# POWER_CONTROL.net
KiCad netlist of a schematic drawn in Altium Designer
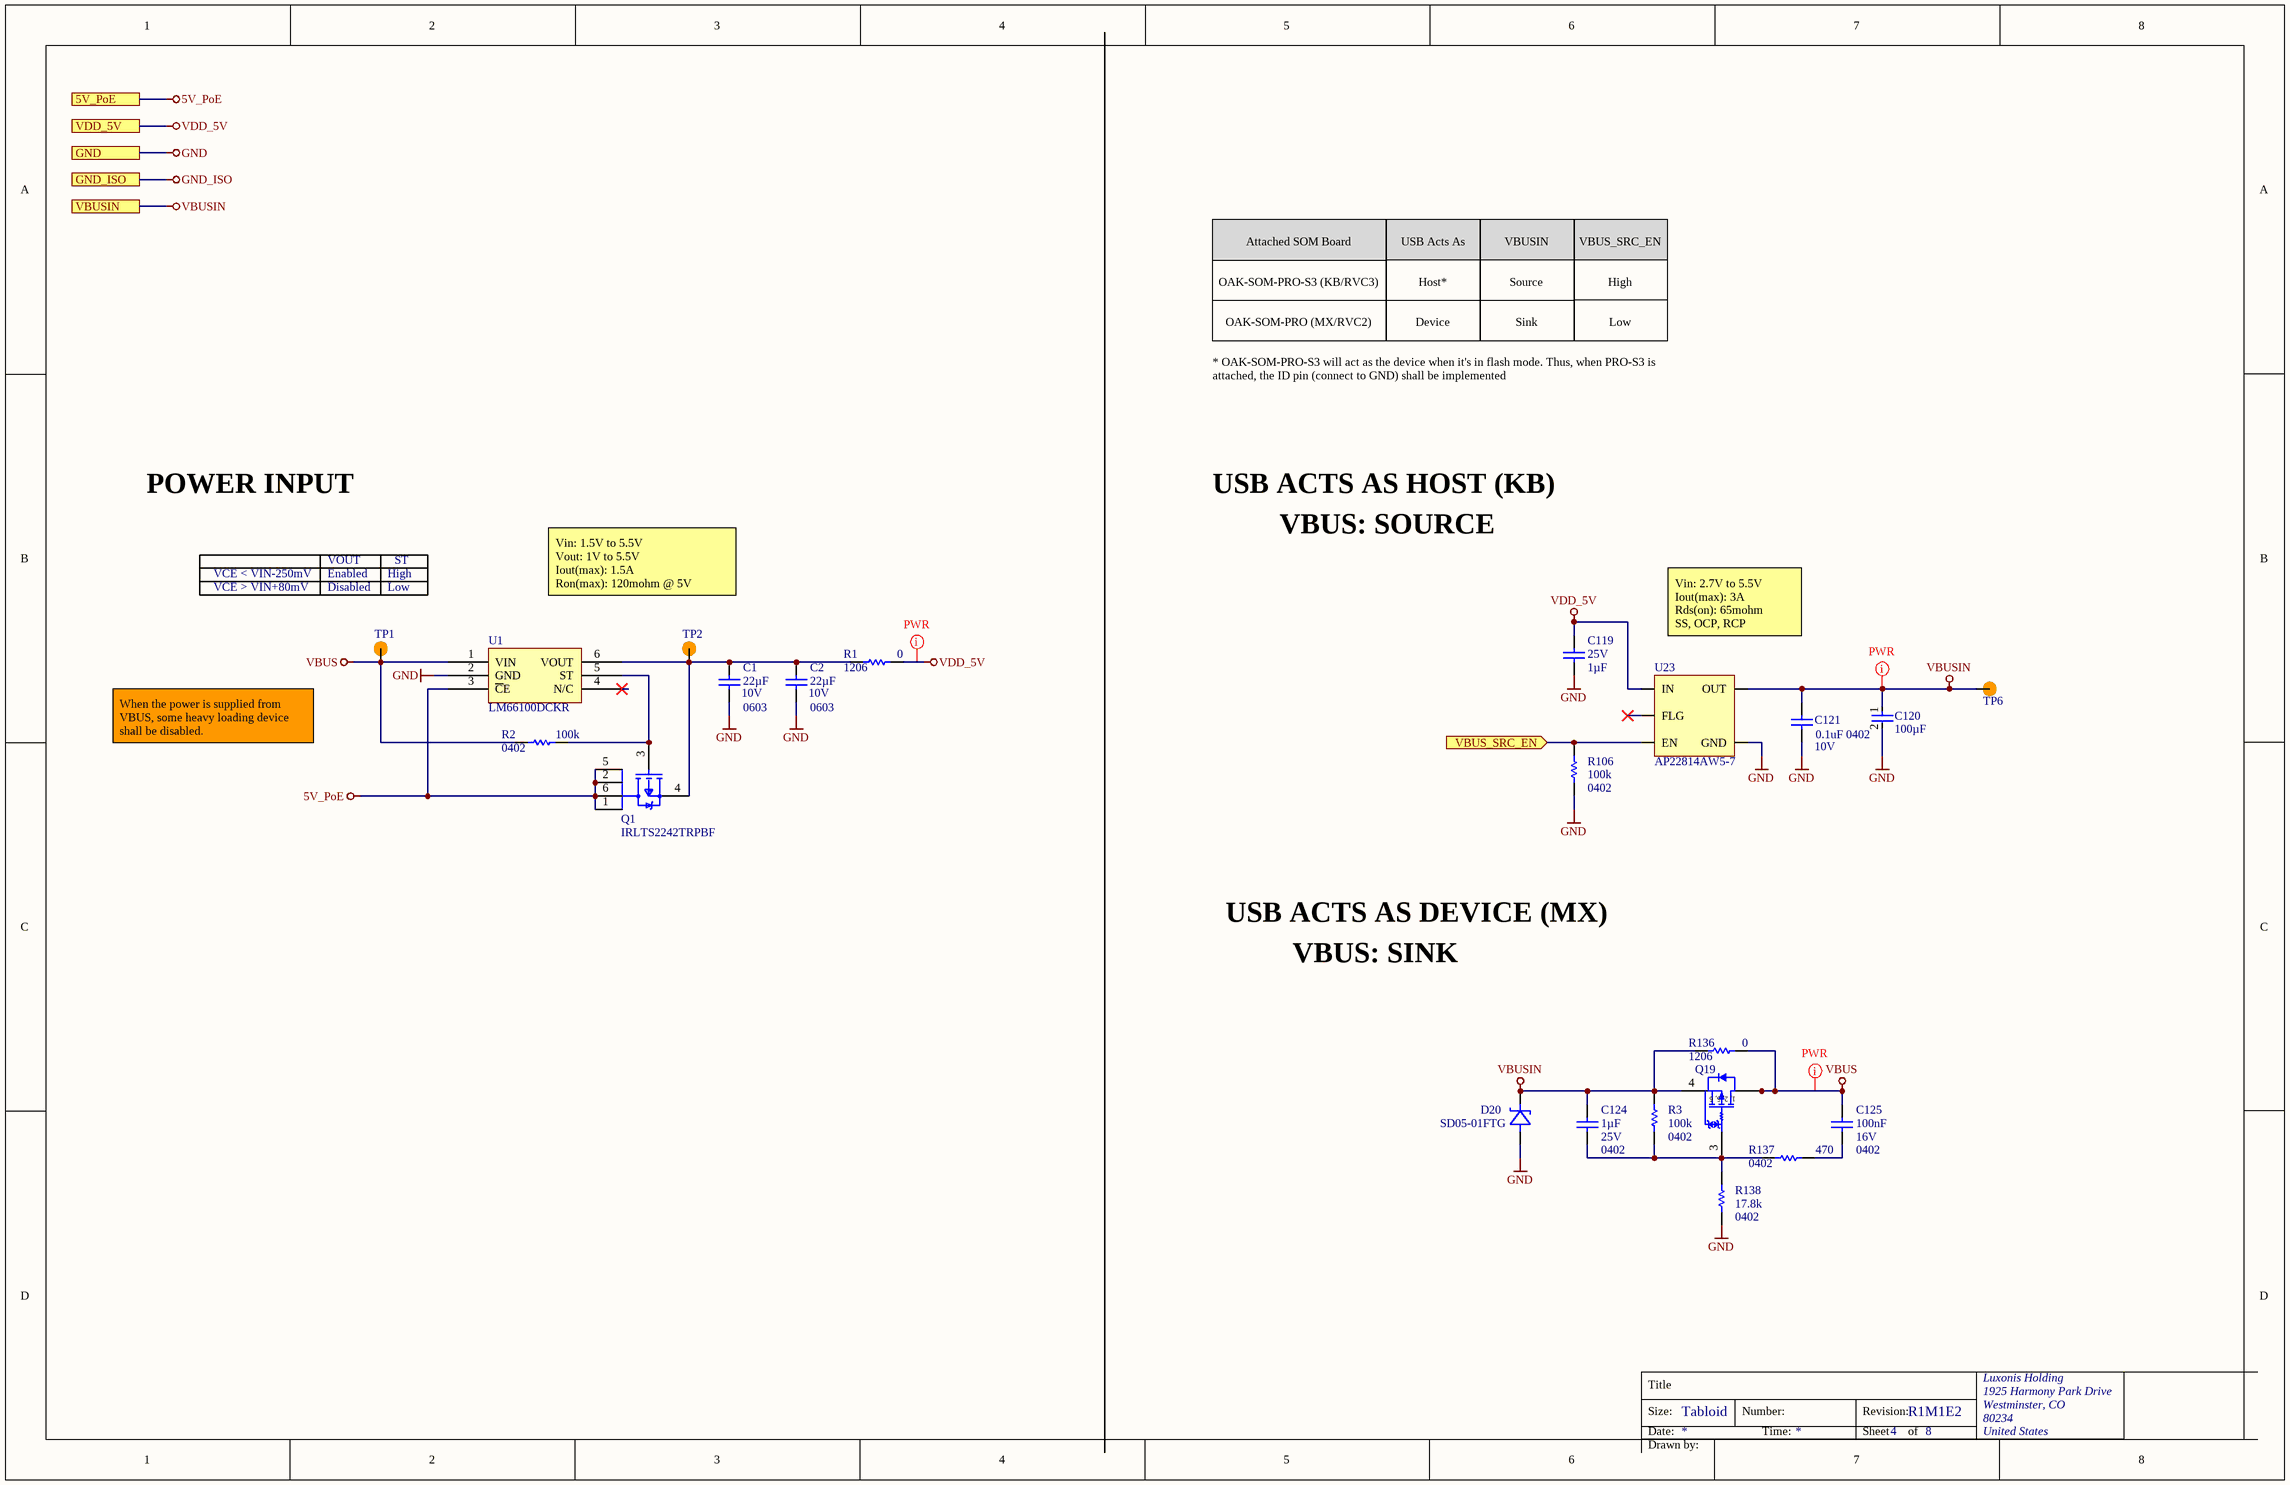
[diagram p0: POWER CONTROL.SchDoc]

(export (version "E")
  (design (tool "Eeschema 10.0.6"))
  (components
    (comp (ref "C1")
      (value "22µF")
      (footprint "CAPC0603(1608)100_N")
      (description "CAP CER 22UF 10V X5R 0603 20%")
      (fields
        (field (name "VOLTAGE RATING") "10V")
        (field (name "TOLERANCE") "20%")
        (field (name "CASE/PACKAGE") "0603")
        (field (name "Comment") "GRM188R61A226ME15D")
      )
      (libsource (lib "Luxonis LLC") (part "GRM188R61C475KAAJD"))
    )
    (comp (ref "C2")
      (value "22µF")
      (footprint "CAPC0603(1608)100_N")
      (description "CAP CER 22UF 10V X5R 0603 20%")
      (fields
        (field (name "VOLTAGE RATING") "10V")
        (field (name "TOLERANCE") "20%")
        (field (name "CASE/PACKAGE") "0603")
        (field (name "Comment") "GRM188R61A226ME15D")
      )
      (libsource (lib "Luxonis LLC") (part "GRM188R61C475KAAJD"))
    )
    (comp (ref "C119")
      (value "1µF")
      (footprint "CAPC0402(1005)70_N")
      (description "CAP CER 1UF 25V X5R 0402 10%")
      (fields
        (field (name "VOLTAGE RATING") "25V")
        (field (name "TOLERANCE") "10%")
        (field (name "Comment") "GRM155R61E105KA12D")
      )
      (libsource (lib "Luxonis LLC") (part "GRM188R61C475KAAJD"))
    )
    (comp (ref "C120")
      (value "100µF")
      (footprint "FP-C1210C107M8PACTU-MFG")
      (description "CAP CER 100UF 10V X5R 1210 20%")
      (fields (field (name "TOLERANCE") "20%") (field (name "Comment") "C1210C107M8PACTU"))
      (libsource (lib "Luxonis LLC") (part "b4654b650e69147ec39a6b967a45e02"))
    )
    (comp (ref "C121")
      (value "0.1uF 0402")
      (footprint "CAP_Altium_Vault_Generic:CAPC0402(1005)70_N")
      (description "CAP CER 0.1UF 10V X7R 0402 5%")
      (fields (field (name "TOLERANCE") "5%") (field (name "VOLTAGE RATING") "10V"))
      (libsource (lib "LuxonisMaster") (part "GRM155R71A104JA01D"))
    )
    (comp (ref "C124")
      (value "1µF")
      (footprint "CAPC0402(1005)70_N")
      (description "CAP CER 1UF 25V X5R 0402 10%")
      (fields
        (field (name "VOLTAGE RATING") "25V")
        (field (name "CASE/PACKAGE") "0402")
        (field (name "TOLERANCE") "10%")
        (field (name "Comment") "GRM155R61E105KA12D")
      )
      (libsource (lib "Luxonis LLC") (part "GRM188R61C475KAAJD"))
    )
    (comp (ref "C125")
      (value "100nF")
      (footprint "CAPC0402(1005)60_N")
      (description "CAP CER 0.1UF 16V X7R 0402 10%")
      (fields
        (field (name "VOLTAGE RATING") "16V")
        (field (name "CASE/PACKAGE") "0402")
        (field (name "TOLERANCE") "10%")
        (field (name "Comment") "CL05B104KO5NFNC")
      )
      (libsource (lib "Luxonis LLC") (part "GRM188R61C475KAAJD"))
    )
    (comp (ref "D20")
      (value "SD05-01FTG")
      (footprint "SD05-01FTG-Footprint-1")
      (description "Trans Voltage Suppressor Diode, 450W, 5V V(RWM), Unidirectional, 1 Element")
      (libsource (lib "Luxonis LLC") (part "SD05-01FTG"))
    )
    (comp (ref "Q1")
      (value "IRLTS2242TRPBF")
      (footprint "TSOP-6-MFG")
      (description "MOSFET P-CH 20V 6.9A 6TSOP")
      (libsource (lib "Luxonis LLC") (part "IRLTS2242TRPBF"))
    )
    (comp (ref "Q19")
      (value "NTJS4151PT1G")
      (footprint "ONSC-SC70-6-419B-02_W_V")
      (description "Trench Power MOSFET, -20 V, -4.2 A, Single P-Channel, 6-Pin SC70, Pb-Free, Tape and Reel")
      (libsource (lib "Luxonis LLC") (part "NTJS4151PT1G"))
    )
    (comp (ref "R1")
      (value "0")
      (footprint "RESC3116X70X50ML13T20")
      (description "RES SMD 0 OHM 5% 0.25W 1206")
      (fields
        (field (name "CASE/PACKAGE") "1206")
        (field (name "TOLERANCE") "5%")
        (field (name "Comment") "ERJ8GEY0R00V")
      )
      (libsource (lib "Luxonis LLC") (part "Default resistor symbol"))
    )
    (comp (ref "R2")
      (value "100k")
      (footprint "RESC0402(1005)_L")
      (description "RES SMD 100K OHM 1% 1/16W 0402")
      (fields
        (field (name "CASE/PACKAGE") "0402")
        (field (name "TOLERANCE") "1%")
        (field (name "Comment") "RC0402FR-07100KL")
      )
      (libsource (lib "Luxonis LLC") (part "Default resistor symbol"))
    )
    (comp (ref "R3")
      (value "100k")
      (footprint "RESC0402(1005)_L")
      (description "RES SMD 100K OHM 1% 1/16W 0402")
      (fields
        (field (name "CASE/PACKAGE") "0402")
        (field (name "TOLERANCE") "1%")
        (field (name "Comment") "RC0402FR-07100KL")
      )
      (libsource (lib "Luxonis LLC") (part "Default resistor symbol"))
    )
    (comp (ref "R106")
      (value "100k")
      (footprint "RESC0402(1005)_L")
      (description "RES SMD 100K OHM 1% 1/16W 0402")
      (fields
        (field (name "CASE/PACKAGE") "0402")
        (field (name "TOLERANCE") "1%")
        (field (name "Comment") "RC0402FR-07100KL")
      )
      (libsource (lib "Luxonis LLC") (part "Default resistor symbol"))
    )
    (comp (ref "R136")
      (value "0")
      (footprint "RESC3116X70X50ML13T20")
      (description "RES SMD 0 OHM 5% 0.25W 1206")
      (fields
        (field (name "CASE/PACKAGE") "1206")
        (field (name "TOLERANCE") "5%")
        (field (name "Comment") "ERJ8GEY0R00V")
      )
      (libsource (lib "Luxonis LLC") (part "Default resistor symbol"))
    )
    (comp (ref "R137")
      (value "470")
      (footprint "RESC0402(1005)_L")
      (description "RES SMD 470 OHM 1% 1/16W 0402")
      (fields
        (field (name "CASE/PACKAGE") "0402")
        (field (name "TOLERANCE") "1%")
        (field (name "Comment") "CRCW0402470RFKED")
      )
      (libsource (lib "Luxonis LLC") (part "Default resistor symbol"))
    )
    (comp (ref "R138")
      (value "17.8k")
      (footprint "RESC0402(1005)_L")
      (description "RES SMD 17.8K OHM 1% 1/10W 0402")
      (fields
        (field (name "CASE/PACKAGE") "0402")
        (field (name "TOLERANCE") "1%")
        (field (name "Comment") "ERJ-2RKF1782X")
      )
      (libsource (lib "Luxonis LLC") (part "Default resistor symbol"))
    )
    (comp (ref "TP1")
      (value "TP100_200_NS")
      (footprint "TP075_150_NS")
      (libsource (lib "Luxonis LLC") (part "TEST_POINT"))
    )
    (comp (ref "TP2")
      (value "TP100_200_NS")
      (footprint "TP075_150_NS")
      (libsource (lib "Luxonis LLC") (part "TEST_POINT"))
    )
    (comp (ref "TP6")
      (value "TP100_200_NS")
      (footprint "TP075_150_NS")
      (libsource (lib "Luxonis LLC") (part "TEST_POINT"))
    )
    (comp (ref "U1")
      (value "LM66100DCKR")
      (footprint "LM66100DCKR")
      (description "IC OR CTRLR IDEAL DIODE SC70-6")
      (libsource (lib "Luxonis LLC") (part "LM66100DCKR"))
    )
    (comp (ref "U23")
      (value "AP22814AW5-7")
      (footprint "AP22814AW5-7-Footprint-1")
      (description "Single Channel Power Distribution Load Switch, -40 to 85°C, Rohs")
      (libsource (lib "Luxonis LLC") (part "AP22814AW5-7-Symbol-1"))
    )
  )
  (nets
    (net (code "1") (name "/VBUS_SRC_EN") (class "Default")
      (node (ref "R106") (pin "1") (pinfunction "1_1") (pintype "passive"))
      (node (ref "U23") (pin "4") (pinfunction "EN_4") (pintype "passive"))
    )
    (net (code "2") (name "5V_PoE") (class "Default")
      (node (ref "Q1") (pin "1") (pinfunction "D_1") (pintype "passive"))
      (node (ref "Q1") (pin "2") (pinfunction "D_2") (pintype "passive"))
      (node (ref "Q1") (pin "5") (pinfunction "D_5") (pintype "passive"))
      (node (ref "Q1") (pin "6") (pinfunction "D_6") (pintype "passive"))
      (node (ref "U1") (pin "3") (pinfunction "~{C}E_3") (pintype "passive"))
    )
    (net (code "3") (name "GND") (class "Default")
      (node (ref "C1") (pin "1") (pinfunction "1_1") (pintype "passive"))
      (node (ref "C119") (pin "1") (pinfunction "1_1") (pintype "passive"))
      (node (ref "C120") (pin "2") (pinfunction "2_2") (pintype "passive"))
      (node (ref "C121") (pin "1") (pinfunction "1_1") (pintype "passive"))
      (node (ref "C2") (pin "1") (pinfunction "1_1") (pintype "passive"))
      (node (ref "D20") (pin "1") (pinfunction "1_1") (pintype "passive"))
      (node (ref "R106") (pin "2") (pinfunction "2_2") (pintype "passive"))
      (node (ref "R138") (pin "1") (pinfunction "1_1") (pintype "passive"))
      (node (ref "U1") (pin "2") (pinfunction "GND_2") (pintype "passive"))
      (node (ref "U23") (pin "2") (pinfunction "GND_2") (pintype "passive"))
    )
    (net (code "5") (name "Net-(C125-Pad1)") (class "Default")
      (node (ref "C125") (pin "1") (pinfunction "1_1") (pintype "passive"))
      (node (ref "R137") (pin "2") (pinfunction "2_2") (pintype "passive"))
    )
    (net (code "6") (name "Net-(Q1-G)") (class "Default")
      (node (ref "Q1") (pin "3") (pinfunction "G_3") (pintype "passive"))
      (node (ref "R2") (pin "1") (pinfunction "1_1") (pintype "passive"))
      (node (ref "U1") (pin "5") (pinfunction "ST_5") (pintype "passive"))
    )
    (net (code "7") (name "Net-(Q1-S)") (class "Default")
      (node (ref "C1") (pin "2") (pinfunction "2_2") (pintype "passive"))
      (node (ref "C2") (pin "2") (pinfunction "2_2") (pintype "passive"))
      (node (ref "Q1") (pin "4") (pinfunction "S_4") (pintype "passive"))
      (node (ref "R1") (pin "1") (pinfunction "1_1") (pintype "passive"))
      (node (ref "TP2") (pin "1") (pintype "passive"))
      (node (ref "U1") (pin "6") (pinfunction "VOUT_6") (pintype "passive"))
    )
    (net (code "8") (name "Net-(Q19-G)") (class "Default")
      (node (ref "C124") (pin "1") (pinfunction "1_1") (pintype "passive"))
      (node (ref "Q19") (pin "3") (pinfunction "G_3") (pintype "passive"))
      (node (ref "R137") (pin "1") (pinfunction "1_1") (pintype "passive"))
      (node (ref "R138") (pin "2") (pinfunction "2_2") (pintype "passive"))
      (node (ref "R3") (pin "1") (pinfunction "1_1") (pintype "passive"))
    )
    (net (code "9") (name "VBUS") (class "Default")
      (node (ref "C125") (pin "2") (pinfunction "2_2") (pintype "passive"))
      (node (ref "Q19") (pin "1") (pinfunction "D_1") (pintype "passive"))
      (node (ref "Q19") (pin "2") (pinfunction "D_2") (pintype "passive"))
      (node (ref "Q19") (pin "5") (pinfunction "D_5") (pintype "passive"))
      (node (ref "Q19") (pin "6") (pinfunction "D_6") (pintype "passive"))
      (node (ref "R136") (pin "2") (pinfunction "2_2") (pintype "passive"))
      (node (ref "R2") (pin "2") (pinfunction "2_2") (pintype "passive"))
      (node (ref "TP1") (pin "1") (pintype "passive"))
      (node (ref "U1") (pin "1") (pinfunction "VIN_1") (pintype "passive"))
    )
    (net (code "10") (name "VBUSIN") (class "Default")
      (node (ref "C120") (pin "1") (pinfunction "1_1") (pintype "passive"))
      (node (ref "C121") (pin "2") (pinfunction "2_2") (pintype "passive"))
      (node (ref "C124") (pin "2") (pinfunction "2_2") (pintype "passive"))
      (node (ref "D20") (pin "2") (pinfunction "2_2") (pintype "passive"))
      (node (ref "Q19") (pin "4") (pinfunction "S_4") (pintype "passive"))
      (node (ref "R136") (pin "1") (pinfunction "1_1") (pintype "passive"))
      (node (ref "R3") (pin "2") (pinfunction "2_2") (pintype "passive"))
      (node (ref "TP6") (pin "1") (pintype "passive"))
      (node (ref "U23") (pin "1") (pinfunction "OUT_1") (pintype "passive"))
    )
    (net (code "11") (name "VDD_5V") (class "Default")
      (node (ref "C119") (pin "2") (pinfunction "2_2") (pintype "passive"))
      (node (ref "R1") (pin "2") (pinfunction "2_2") (pintype "passive"))
      (node (ref "U23") (pin "5") (pinfunction "IN_5") (pintype "passive"))
    )
    (net (code "12") (name "unconnected-(U1-N{slash}C-Pad4)") (class "Default")
      (node (ref "U1") (pin "4") (pinfunction "N/C_4") (pintype "passive+no_connect"))
    )
    (net (code "13") (name "unconnected-(U23-FLG-Pad3)") (class "Default")
      (node (ref "U23") (pin "3") (pinfunction "FLG_3") (pintype "passive+no_connect"))
    )
  )
)
